# T07_411rev_4.net
KiCad netlist of a schematic drawn in EAGLE
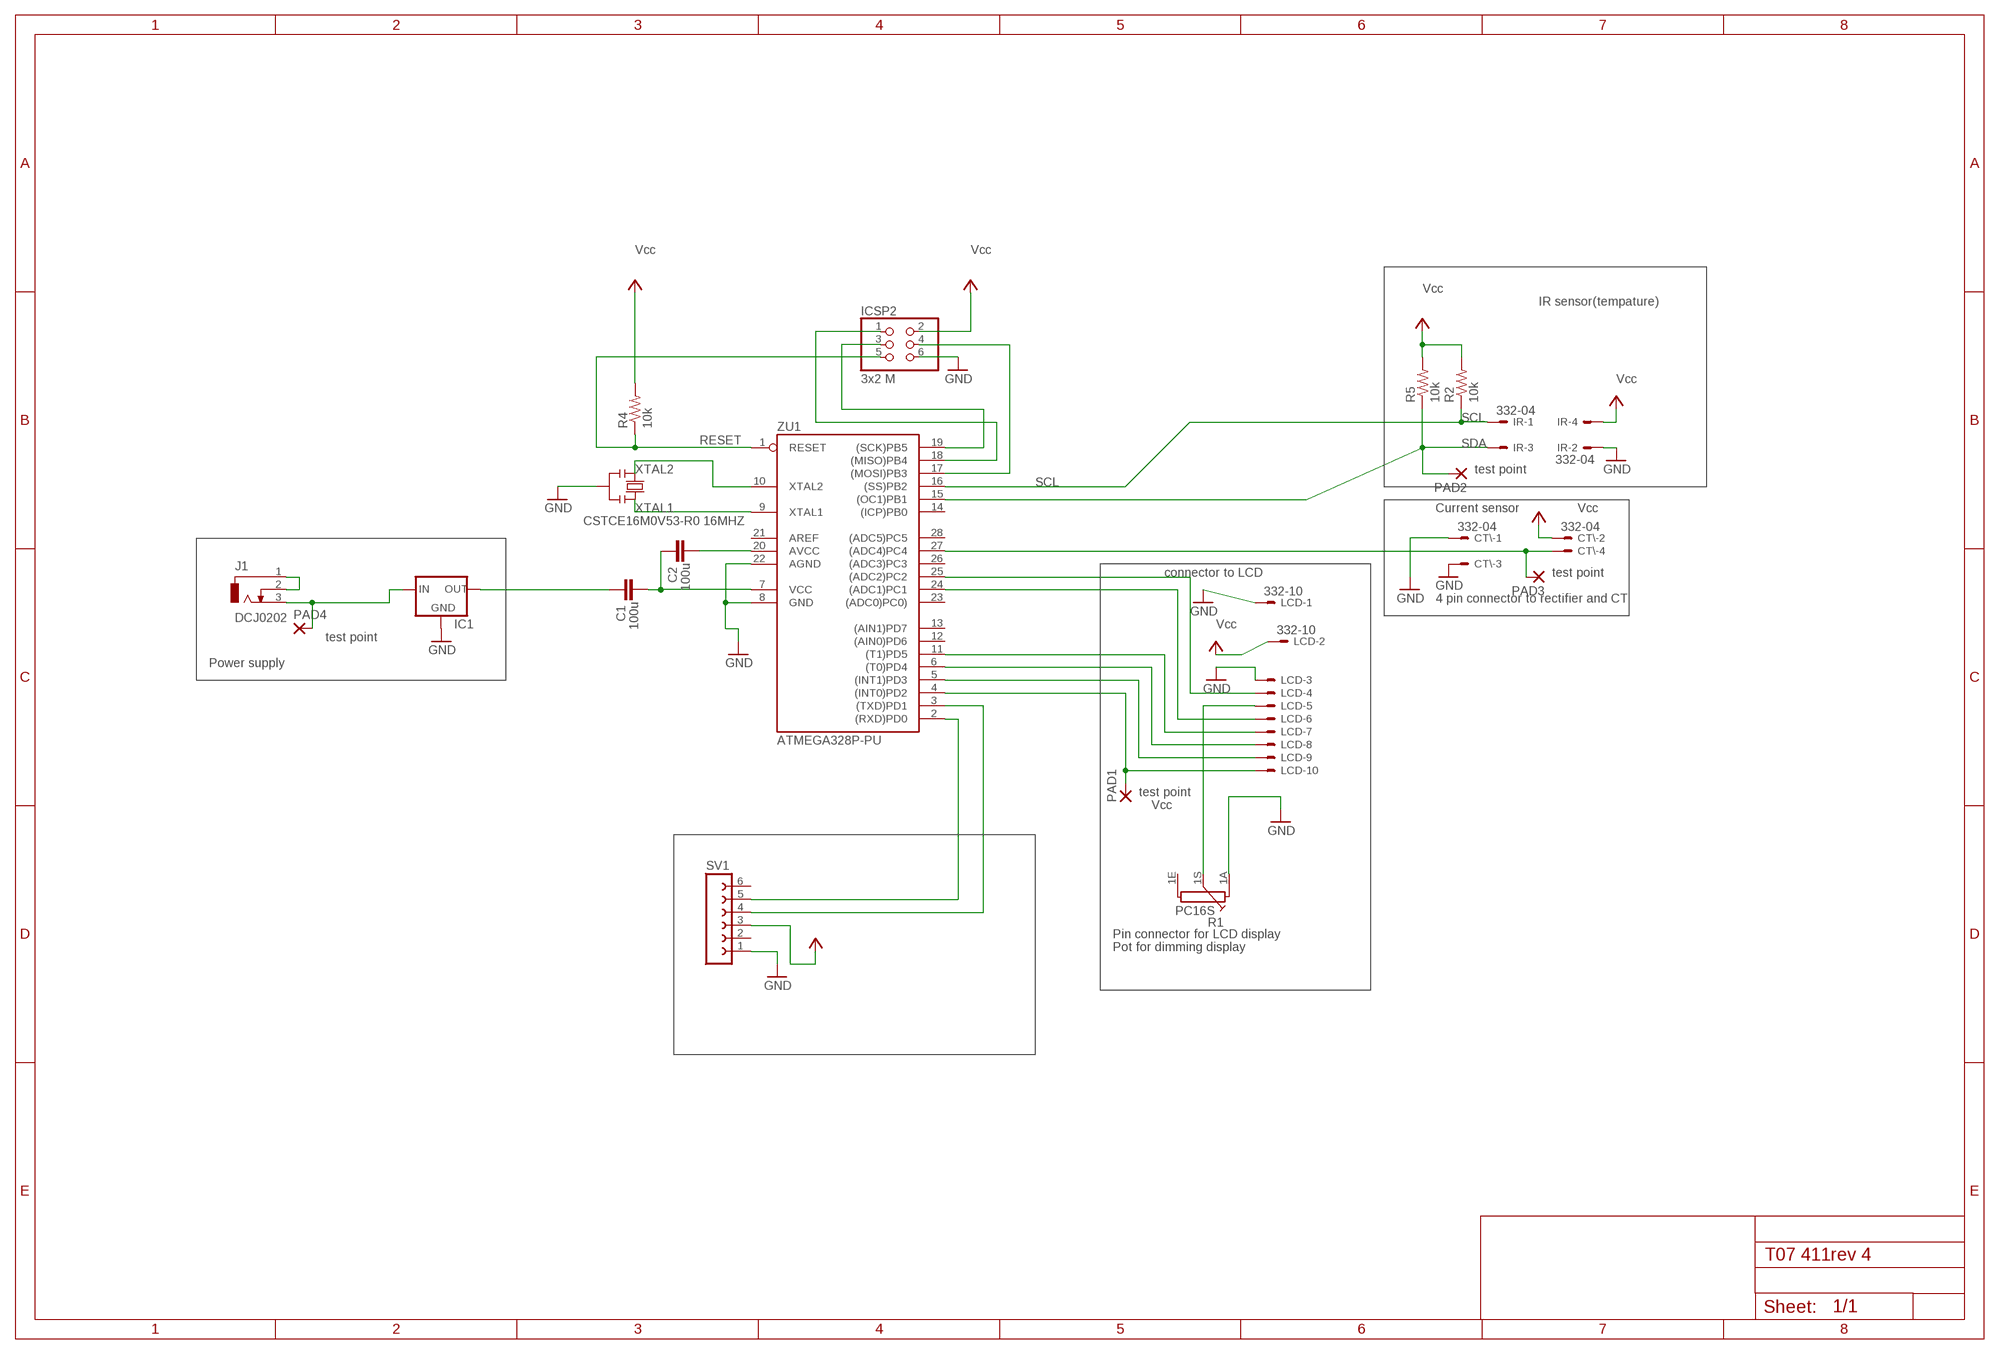
[diagram p0: schematic, sheet 1]

(export (version "E")
  (design (tool "Eeschema 10.0.6"))
  (components
    (comp (ref "C1")
      (value "100u")
      (footprint "eagle-import:C0603-ROUND")
      (libsource (lib "eagle-import") (part "C-EU0603-RND"))
    )
    (comp (ref "C2")
      (value "100u")
      (footprint "eagle-import:C0603-ROUND")
      (libsource (lib "eagle-import") (part "C-EU0603-RND"))
    )
    (comp (ref "CT\\")
      (value "332-04")
      (footprint "eagle-import:332-04")
      (libsource (lib "eagle-import") (part "332-04"))
    )
    (comp (ref "IC1")
      (value "78XXL")
      (footprint "eagle-import:78XXL")
      (libsource (lib "eagle-import") (part "78XXL"))
    )
    (comp (ref "ICSP2")
      (value "3x2 M")
      (footprint "eagle-import:2X03")
      (libsource (lib "eagle-import") (part "PINHD-2X3"))
    )
    (comp (ref "IR")
      (value "332-04")
      (footprint "eagle-import:332-04")
      (libsource (lib "eagle-import") (part "332-04"))
    )
    (comp (ref "J1")
      (value "DCJ0202")
      (footprint "eagle-import:DCJ0202")
      (libsource (lib "eagle-import") (part "DCJ0202"))
    )
    (comp (ref "LCD")
      (value "332-10")
      (footprint "eagle-import:332-10")
      (libsource (lib "eagle-import") (part "332-10"))
    )
    (comp (ref "PAD1")
      (value "1,6/0,9")
      (footprint "eagle-import:1,6_0,9")
      (libsource (lib "eagle-import") (part "1,6/0,9"))
    )
    (comp (ref "PAD2")
      (value "1,6/0,9")
      (footprint "eagle-import:1,6_0,9")
      (libsource (lib "eagle-import") (part "1,6/0,9"))
    )
    (comp (ref "PAD3")
      (value "1,6/0,9")
      (footprint "eagle-import:1,6_0,9")
      (libsource (lib "eagle-import") (part "1,6/0,9"))
    )
    (comp (ref "PAD4")
      (value "1,6/0,9")
      (footprint "eagle-import:1,6_0,9")
      (libsource (lib "eagle-import") (part "1,6/0,9"))
    )
    (comp (ref "R1")
      (value "PC16S")
      (footprint "eagle-import:PC16S")
      (libsource (lib "eagle-import") (part "PC16S"))
    )
    (comp (ref "R2")
      (value "10k")
      (footprint "eagle-import:0402-RES")
      (libsource (lib "eagle-import") (part "RESISTOR0402-RES"))
    )
    (comp (ref "R4")
      (value "10k")
      (footprint "eagle-import:0402-RES")
      (libsource (lib "eagle-import") (part "RESISTOR0402-RES"))
    )
    (comp (ref "R5")
      (value "10k")
      (footprint "eagle-import:0402-RES")
      (libsource (lib "eagle-import") (part "RESISTOR0402-RES"))
    )
    (comp (ref "SV1")
      (value "FE06-1")
      (footprint "eagle-import:FE06")
      (libsource (lib "eagle-import") (part "FE06-1"))
    )
    (comp (ref "Y3")
      (value "CSTCE16M0V53-R0 16MHZ")
      (footprint "eagle-import:RESONATOR")
      (libsource (lib "eagle-import") (part "RESONATORMU"))
    )
    (comp (ref "ZU1")
      (value "ATMEGA328P-PU")
      (footprint "eagle-import:DIL28-3")
      (libsource (lib "eagle-import") (part "ATMEGA328P-PU"))
    )
  )
  (nets
    (net (code "1") (name "+5V") (class "Default")
      (node (ref "CT\\") (pin "2") (pinfunction "S_2") (pintype "passive"))
      (node (ref "ICSP2") (pin "2") (pinfunction "2_2") (pintype "passive"))
      (node (ref "IR") (pin "4") (pinfunction "S_4") (pintype "passive"))
      (node (ref "LCD") (pin "2") (pinfunction "S_2") (pintype "passive"))
      (node (ref "R2") (pin "2") (pinfunction "2_2") (pintype "passive"))
      (node (ref "R4") (pin "2") (pinfunction "2_2") (pintype "passive"))
      (node (ref "R5") (pin "2") (pinfunction "2_2") (pintype "passive"))
      (node (ref "SV1") (pin "3") (pinfunction "3_3") (pintype "passive"))
    )
    (net (code "2") (name "/RESET") (class "Default")
      (node (ref "ICSP2") (pin "5") (pinfunction "5_5") (pintype "passive"))
      (node (ref "R4") (pin "1") (pinfunction "1_1") (pintype "passive"))
      (node (ref "ZU1") (pin "1") (pinfunction "RESET_1") (pintype "input"))
    )
    (net (code "3") (name "/SCL") (class "Default")
      (node (ref "IR") (pin "1") (pinfunction "S_1") (pintype "passive"))
      (node (ref "R2") (pin "1") (pinfunction "1_1") (pintype "passive"))
      (node (ref "ZU1") (pin "16") (pinfunction "(SS)PB2_16") (pintype "bidirectional"))
    )
    (net (code "4") (name "/SDA") (class "Default")
      (node (ref "IR") (pin "3") (pinfunction "S_3") (pintype "passive"))
      (node (ref "PAD2") (pin "1") (pinfunction "P_1") (pintype "passive"))
      (node (ref "R5") (pin "1") (pinfunction "1_1") (pintype "passive"))
      (node (ref "ZU1") (pin "15") (pinfunction "(OC1)PB1_15") (pintype "bidirectional"))
    )
    (net (code "5") (name "/XTAL1") (class "Default")
      (node (ref "Y3") (pin "3") (pinfunction "3_3") (pintype "passive"))
      (node (ref "ZU1") (pin "9") (pinfunction "XTAL1_9") (pintype "bidirectional"))
    )
    (net (code "6") (name "/XTAL2") (class "Default")
      (node (ref "Y3") (pin "1") (pinfunction "1_1") (pintype "passive"))
      (node (ref "ZU1") (pin "10") (pinfunction "XTAL2_10") (pintype "bidirectional"))
    )
    (net (code "7") (name "GND") (class "Default")
      (node (ref "CT\\") (pin "1") (pinfunction "S_1") (pintype "passive"))
      (node (ref "CT\\") (pin "3") (pinfunction "S_3") (pintype "passive"))
      (node (ref "IC1") (pin "GND") (pinfunction "GND_GND") (pintype "input"))
      (node (ref "ICSP2") (pin "6") (pinfunction "6_6") (pintype "passive"))
      (node (ref "IR") (pin "2") (pinfunction "S_2") (pintype "passive"))
      (node (ref "LCD") (pin "1") (pinfunction "S_1") (pintype "passive"))
      (node (ref "LCD") (pin "3") (pinfunction "S_3") (pintype "passive"))
      (node (ref "R1") (pin "1A") (pinfunction "1A_1A") (pintype "passive"))
      (node (ref "SV1") (pin "1") (pinfunction "1_1") (pintype "passive"))
      (node (ref "Y3") (pin "2") (pinfunction "2_2") (pintype "passive"))
      (node (ref "ZU1") (pin "22") (pinfunction "AGND_22") (pintype "power_in"))
      (node (ref "ZU1") (pin "8") (pinfunction "GND_8") (pintype "power_in"))
    )
    (net (code "8") (name "Net-(C1-Pad2)") (class "Default")
      (node (ref "C1") (pin "2") (pinfunction "2_2") (pintype "passive"))
      (node (ref "IC1") (pin "OUT") (pinfunction "OUT_OUT") (pintype "passive"))
    )
    (net (code "9") (name "Net-(CT\\D-S)") (class "Default")
      (node (ref "CT\\") (pin "4") (pinfunction "S_4") (pintype "passive"))
      (node (ref "PAD3") (pin "1") (pinfunction "P_1") (pintype "passive"))
      (node (ref "ZU1") (pin "27") (pinfunction "(ADC4)PC4_27") (pintype "bidirectional"))
    )
    (net (code "10") (name "Net-(J1-Pad1)") (class "Default")
      (node (ref "J1") (pin "1") (pinfunction "1_1") (pintype "passive"))
      (node (ref "J1") (pin "2") (pinfunction "2_2") (pintype "passive"))
    )
    (net (code "11") (name "Net-(LCDB-S)") (class "Default")
      (node (ref "LCD") (pin "10") (pinfunction "S_10") (pintype "passive"))
      (node (ref "PAD1") (pin "1") (pinfunction "P_1") (pintype "passive"))
      (node (ref "ZU1") (pin "4") (pinfunction "(INT0)PD2_4") (pintype "bidirectional"))
    )
    (net (code "12") (name "Net-(LCDE-S)") (class "Default")
      (node (ref "LCD") (pin "4") (pinfunction "S_4") (pintype "passive"))
      (node (ref "ZU1") (pin "25") (pinfunction "(ADC2)PC2_25") (pintype "bidirectional"))
    )
    (net (code "13") (name "Net-(LCDF-S)") (class "Default")
      (node (ref "LCD") (pin "5") (pinfunction "S_5") (pintype "passive"))
      (node (ref "R1") (pin "1S") (pinfunction "1S_1S") (pintype "passive"))
    )
    (net (code "14") (name "Net-(LCDG-S)") (class "Default")
      (node (ref "LCD") (pin "6") (pinfunction "S_6") (pintype "passive"))
      (node (ref "ZU1") (pin "24") (pinfunction "(ADC1)PC1_24") (pintype "bidirectional"))
    )
    (net (code "15") (name "Net-(LCDH-S)") (class "Default")
      (node (ref "LCD") (pin "7") (pinfunction "S_7") (pintype "passive"))
      (node (ref "ZU1") (pin "11") (pinfunction "(T1)PD5_11") (pintype "bidirectional"))
    )
    (net (code "16") (name "Net-(LCDI-S)") (class "Default")
      (node (ref "LCD") (pin "8") (pinfunction "S_8") (pintype "passive"))
      (node (ref "ZU1") (pin "6") (pinfunction "(T0)PD4_6") (pintype "bidirectional"))
    )
    (net (code "17") (name "Net-(LCDJ-S)") (class "Default")
      (node (ref "LCD") (pin "9") (pinfunction "S_9") (pintype "passive"))
      (node (ref "ZU1") (pin "5") (pinfunction "(INT1)PD3_5") (pintype "bidirectional"))
    )
    (net (code "18") (name "Net-(PAD4-P)") (class "Default")
      (node (ref "IC1") (pin "IN") (pinfunction "IN_IN") (pintype "input"))
      (node (ref "J1") (pin "3") (pinfunction "3_3") (pintype "passive"))
      (node (ref "PAD4") (pin "1") (pinfunction "P_1") (pintype "passive"))
    )
    (net (code "19") (name "Net-(ZU1-(MISO)PB4)") (class "Default")
      (node (ref "ICSP2") (pin "1") (pinfunction "1_1") (pintype "passive"))
      (node (ref "ZU1") (pin "18") (pinfunction "(MISO)PB4_18") (pintype "bidirectional"))
    )
    (net (code "20") (name "Net-(ZU1-(MOSI)PB3)") (class "Default")
      (node (ref "ICSP2") (pin "4") (pinfunction "4_4") (pintype "passive"))
      (node (ref "ZU1") (pin "17") (pinfunction "(MOSI)PB3_17") (pintype "bidirectional"))
    )
    (net (code "21") (name "Net-(ZU1-(RXD)PD0)") (class "Default")
      (node (ref "SV1") (pin "5") (pinfunction "5_5") (pintype "passive"))
      (node (ref "ZU1") (pin "2") (pinfunction "(RXD)PD0_2") (pintype "bidirectional"))
    )
    (net (code "22") (name "Net-(ZU1-(SCK)PB5)") (class "Default")
      (node (ref "ICSP2") (pin "3") (pinfunction "3_3") (pintype "passive"))
      (node (ref "ZU1") (pin "19") (pinfunction "(SCK)PB5_19") (pintype "bidirectional"))
    )
    (net (code "23") (name "Net-(ZU1-(TXD)PD1)") (class "Default")
      (node (ref "SV1") (pin "4") (pinfunction "4_4") (pintype "passive"))
      (node (ref "ZU1") (pin "3") (pinfunction "(TXD)PD1_3") (pintype "bidirectional"))
    )
    (net (code "24") (name "Net-(ZU1-AVCC)") (class "Default")
      (node (ref "C2") (pin "1") (pinfunction "1_1") (pintype "passive"))
      (node (ref "ZU1") (pin "20") (pinfunction "AVCC_20") (pintype "power_in"))
    )
    (net (code "25") (name "Net-(ZU1-VCC)") (class "Default")
      (node (ref "C1") (pin "1") (pinfunction "1_1") (pintype "passive"))
      (node (ref "C2") (pin "2") (pinfunction "2_2") (pintype "passive"))
      (node (ref "ZU1") (pin "7") (pinfunction "VCC_7") (pintype "power_in"))
    )
    (net (code "26") (name "unconnected-(R1-Pad1E)") (class "Default")
      (node (ref "R1") (pin "1E") (pinfunction "1E_1E") (pintype "passive"))
    )
    (net (code "27") (name "unconnected-(SV1-Pad2)") (class "Default")
      (node (ref "SV1") (pin "2") (pinfunction "2_2") (pintype "passive"))
    )
    (net (code "28") (name "unconnected-(SV1-Pad6)") (class "Default")
      (node (ref "SV1") (pin "6") (pinfunction "6_6") (pintype "passive"))
    )
    (net (code "29") (name "unconnected-(ZU1-(ADC0)PC0)-Pad23)") (class "Default")
      (node (ref "ZU1") (pin "23") (pinfunction "(ADC0)PC0)_23") (pintype "bidirectional"))
    )
    (net (code "30") (name "unconnected-(ZU1-(ADC3)PC3-Pad26)") (class "Default")
      (node (ref "ZU1") (pin "26") (pinfunction "(ADC3)PC3_26") (pintype "bidirectional"))
    )
    (net (code "31") (name "unconnected-(ZU1-(ADC5)PC5-Pad28)") (class "Default")
      (node (ref "ZU1") (pin "28") (pinfunction "(ADC5)PC5_28") (pintype "bidirectional"))
    )
    (net (code "32") (name "unconnected-(ZU1-(AIN0)PD6-Pad12)") (class "Default")
      (node (ref "ZU1") (pin "12") (pinfunction "(AIN0)PD6_12") (pintype "bidirectional"))
    )
    (net (code "33") (name "unconnected-(ZU1-(AIN1)PD7-Pad13)") (class "Default")
      (node (ref "ZU1") (pin "13") (pinfunction "(AIN1)PD7_13") (pintype "bidirectional"))
    )
    (net (code "34") (name "unconnected-(ZU1-(ICP)PB0-Pad14)") (class "Default")
      (node (ref "ZU1") (pin "14") (pinfunction "(ICP)PB0_14") (pintype "bidirectional"))
    )
    (net (code "35") (name "unconnected-(ZU1-AREF-Pad21)") (class "Default")
      (node (ref "ZU1") (pin "21") (pinfunction "AREF_21") (pintype "passive"))
    )
  )
)
